# 1-Schematic_LNA_Bias_Tee_powered_SMD_ENC.net
KiCad netlist of a schematic drawn in EasyEDA
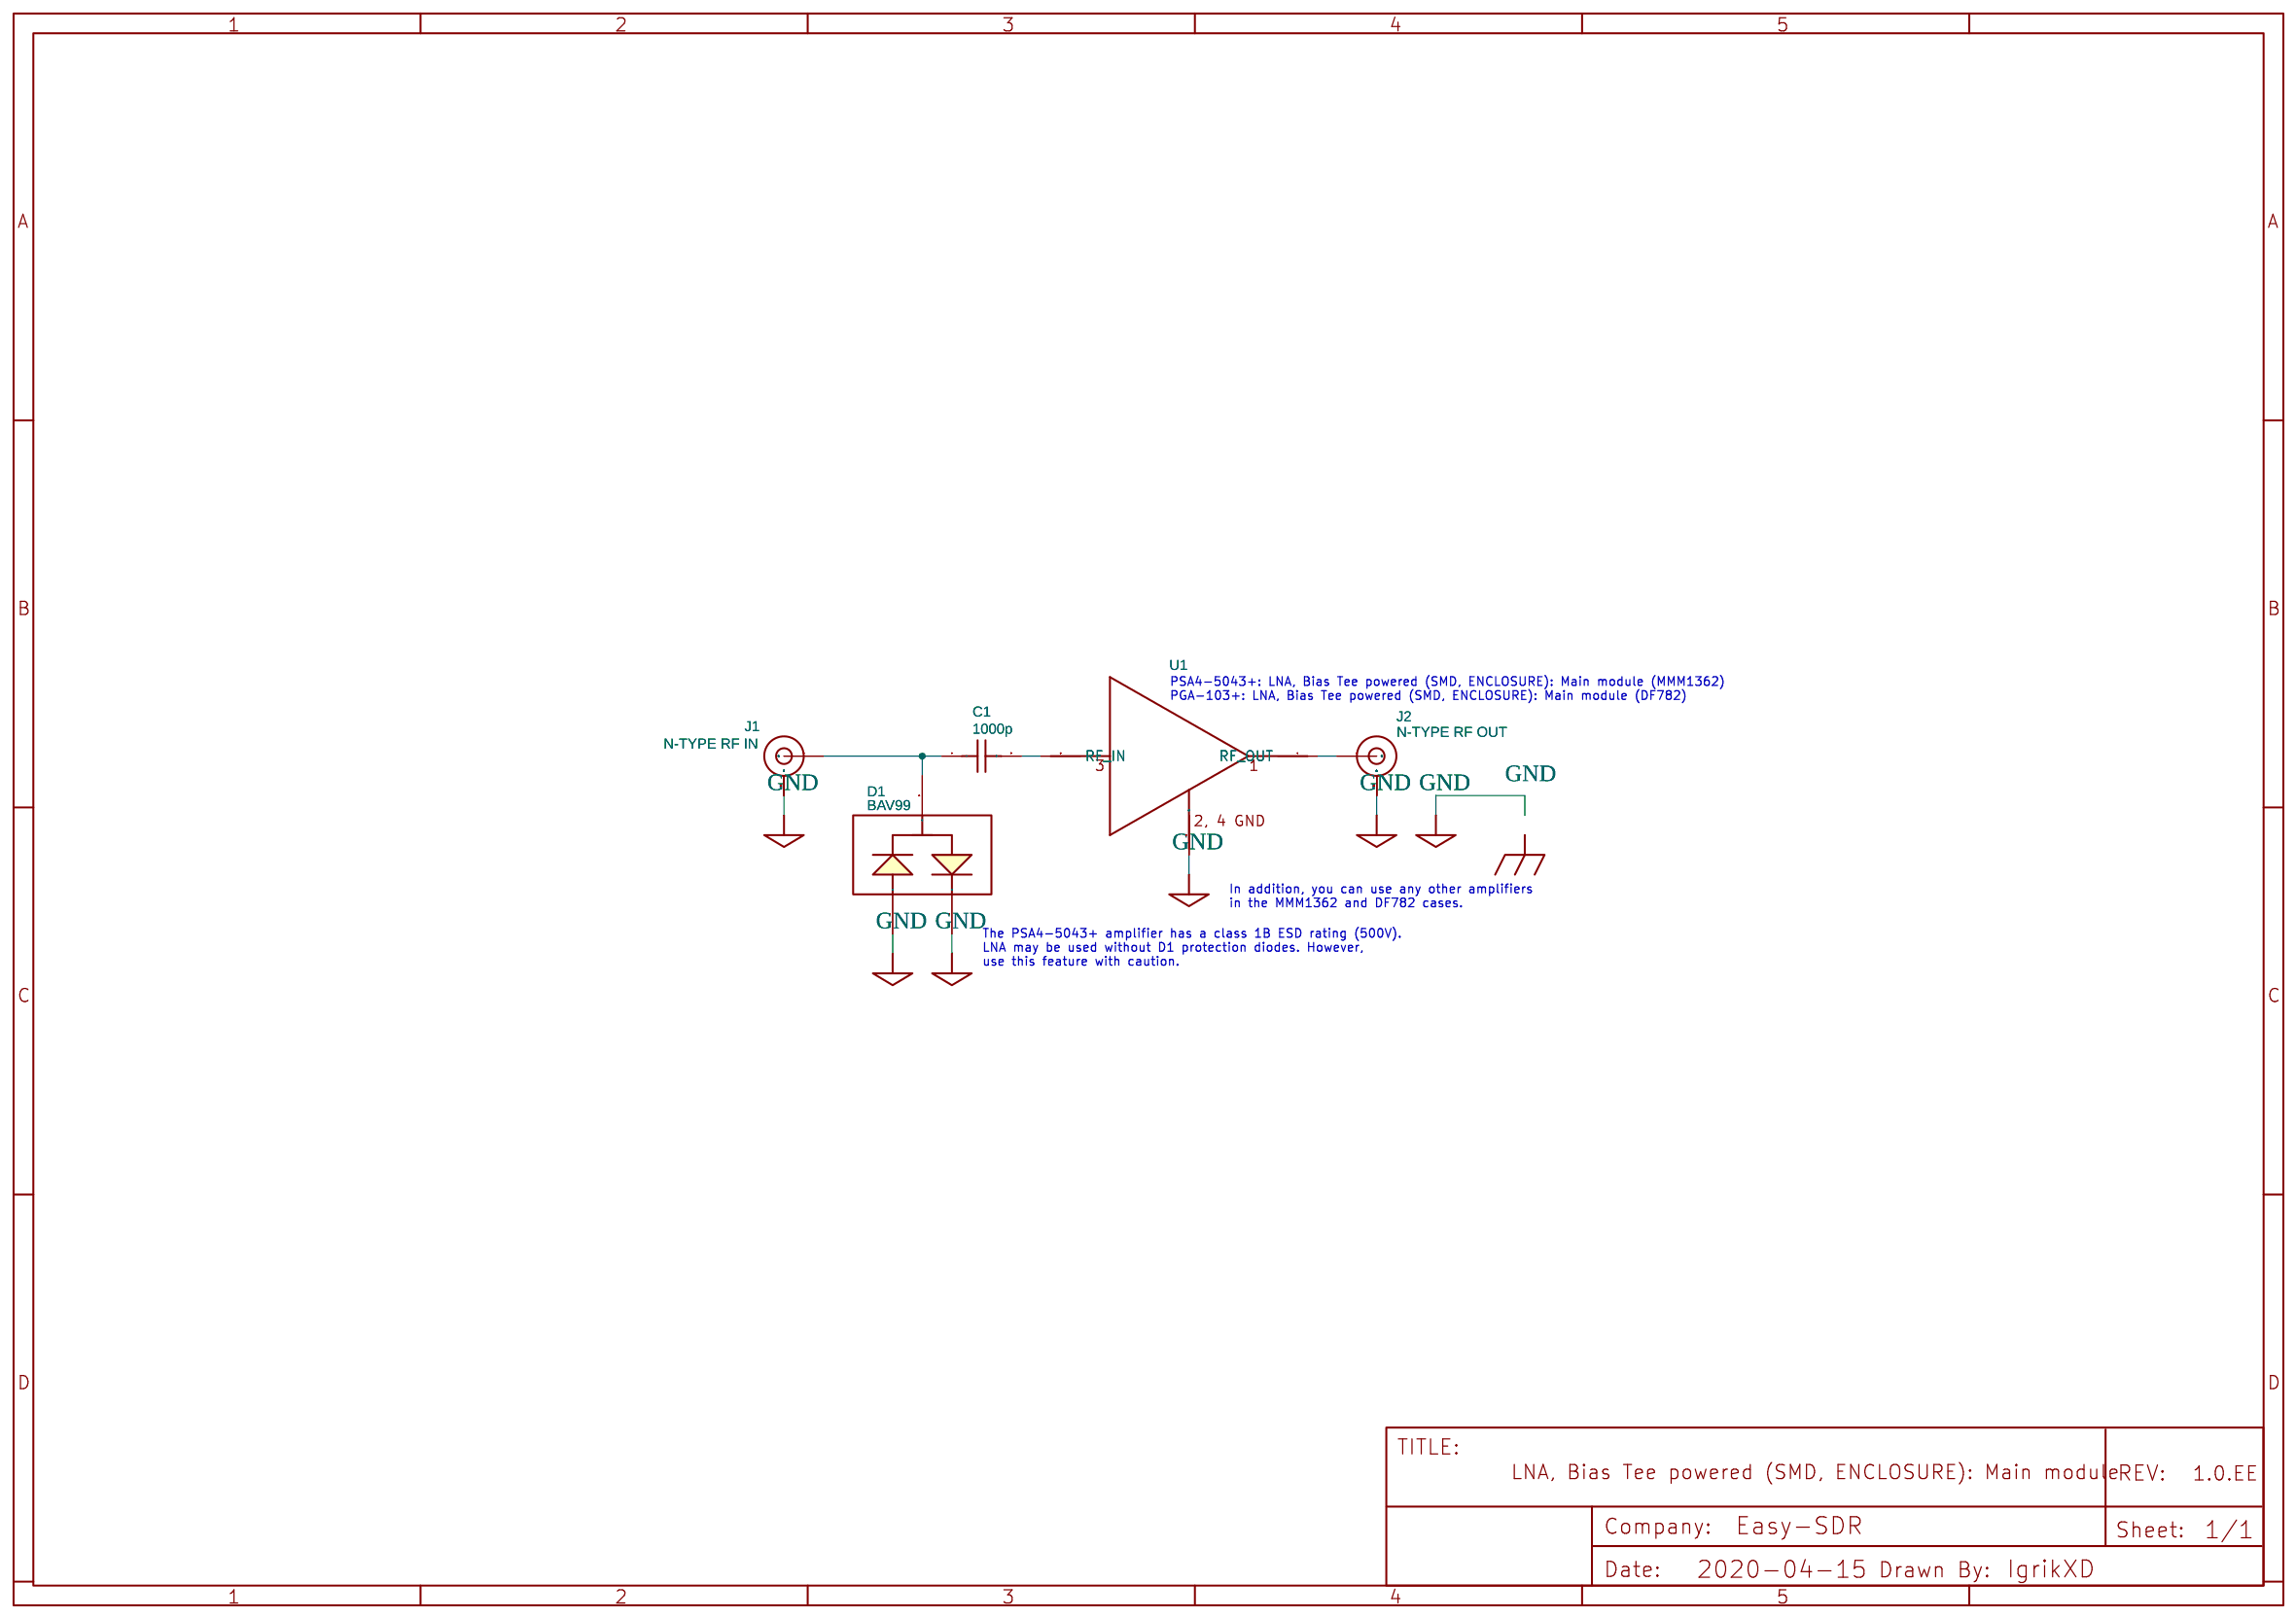
[diagram p0: schematic sheet]

(export (version "E")
  (design (tool "Eeschema 10.0.6"))
  (components
    (comp (ref "C1")
      (value "1000p")
      (fields
        (field (name "BOM_Manufacturer Part") "0603N102G500CT")
        (field (name "BOM_Supplier Part") "C338154")
      )
      (libsource (lib "") (part "Capacitor"))
    )
    (comp (ref "D1")
      (value "BAV99")
      (fields (field (name "BOM_Supplier Part") "C83868"))
      (libsource (lib "") (part "Unknown_460_-370"))
    )
    (comp (ref "J1")
      (value "N-TYPE RF IN")
      (fields
        (field (name "BOM_Manufacturer Part") "82-97-RFX")
        (field (name "BOM_Supplier Part") "ARFX1023-ND")
      )
      (libsource (lib "") (part "Unknown_395_-410"))
    )
    (comp (ref "J2")
      (value "N-TYPE RF OUT")
      (fields
        (field (name "BOM_Manufacturer Part") "82-97-RFX")
        (field (name "BOM_Supplier Part") "ARFX1023-ND")
      )
      (libsource (lib "") (part "Unknown_685_-410"))
    )
    (comp (ref "U1") (value "PSA4-5043+") (libsource (lib "") (part "PSA4-5043+")))
  )
  (nets
    (net (code "1") (name "GND") (class "Default")
      (node (ref "D1") (pin "1") (pinfunction "1_1") (pintype "unspecified"))
      (node (ref "D1") (pin "2") (pinfunction "2_2") (pintype "unspecified"))
      (node (ref "J1") (pin "1") (pinfunction "GND_1") (pintype "unspecified"))
      (node (ref "J1") (pin "3") (pinfunction "GND_3") (pintype "unspecified"))
      (node (ref "J1") (pin "4") (pinfunction "GND_4") (pintype "unspecified"))
      (node (ref "J1") (pin "5") (pinfunction "GND_5") (pintype "unspecified"))
      (node (ref "J2") (pin "1") (pinfunction "GND_1") (pintype "unspecified"))
      (node (ref "J2") (pin "3") (pinfunction "GND_3") (pintype "unspecified"))
      (node (ref "J2") (pin "4") (pinfunction "GND_4") (pintype "unspecified"))
      (node (ref "J2") (pin "5") (pinfunction "GND_5") (pintype "unspecified"))
      (node (ref "U1") (pin "2") (pinfunction "GND_2") (pintype "unspecified"))
      (node (ref "U1") (pin "4") (pinfunction "GND_4") (pintype "unspecified"))
    )
    (net (code "2") (name "Net-(J1-SIGNAL)") (class "Default")
      (node (ref "C1") (pin "1") (pinfunction "1_1") (pintype "unspecified"))
      (node (ref "D1") (pin "3") (pinfunction "3_3") (pintype "unspecified"))
      (node (ref "J1") (pin "2") (pinfunction "SIGNAL_2") (pintype "unspecified"))
    )
    (net (code "3") (name "Net-(J2-SIGNAL)") (class "Default")
      (node (ref "J2") (pin "2") (pinfunction "SIGNAL_2") (pintype "unspecified"))
      (node (ref "U1") (pin "1") (pinfunction "RF_OUT_1") (pintype "unspecified"))
    )
    (net (code "4") (name "Net-(U1-RF_IN)") (class "Default")
      (node (ref "C1") (pin "2") (pinfunction "2_2") (pintype "unspecified"))
      (node (ref "U1") (pin "3") (pinfunction "RF_IN_3") (pintype "unspecified"))
    )
  )
)
